# RasPiTimePowerSWv_1_6.net
KiCad netlist of a schematic drawn in EAGLE
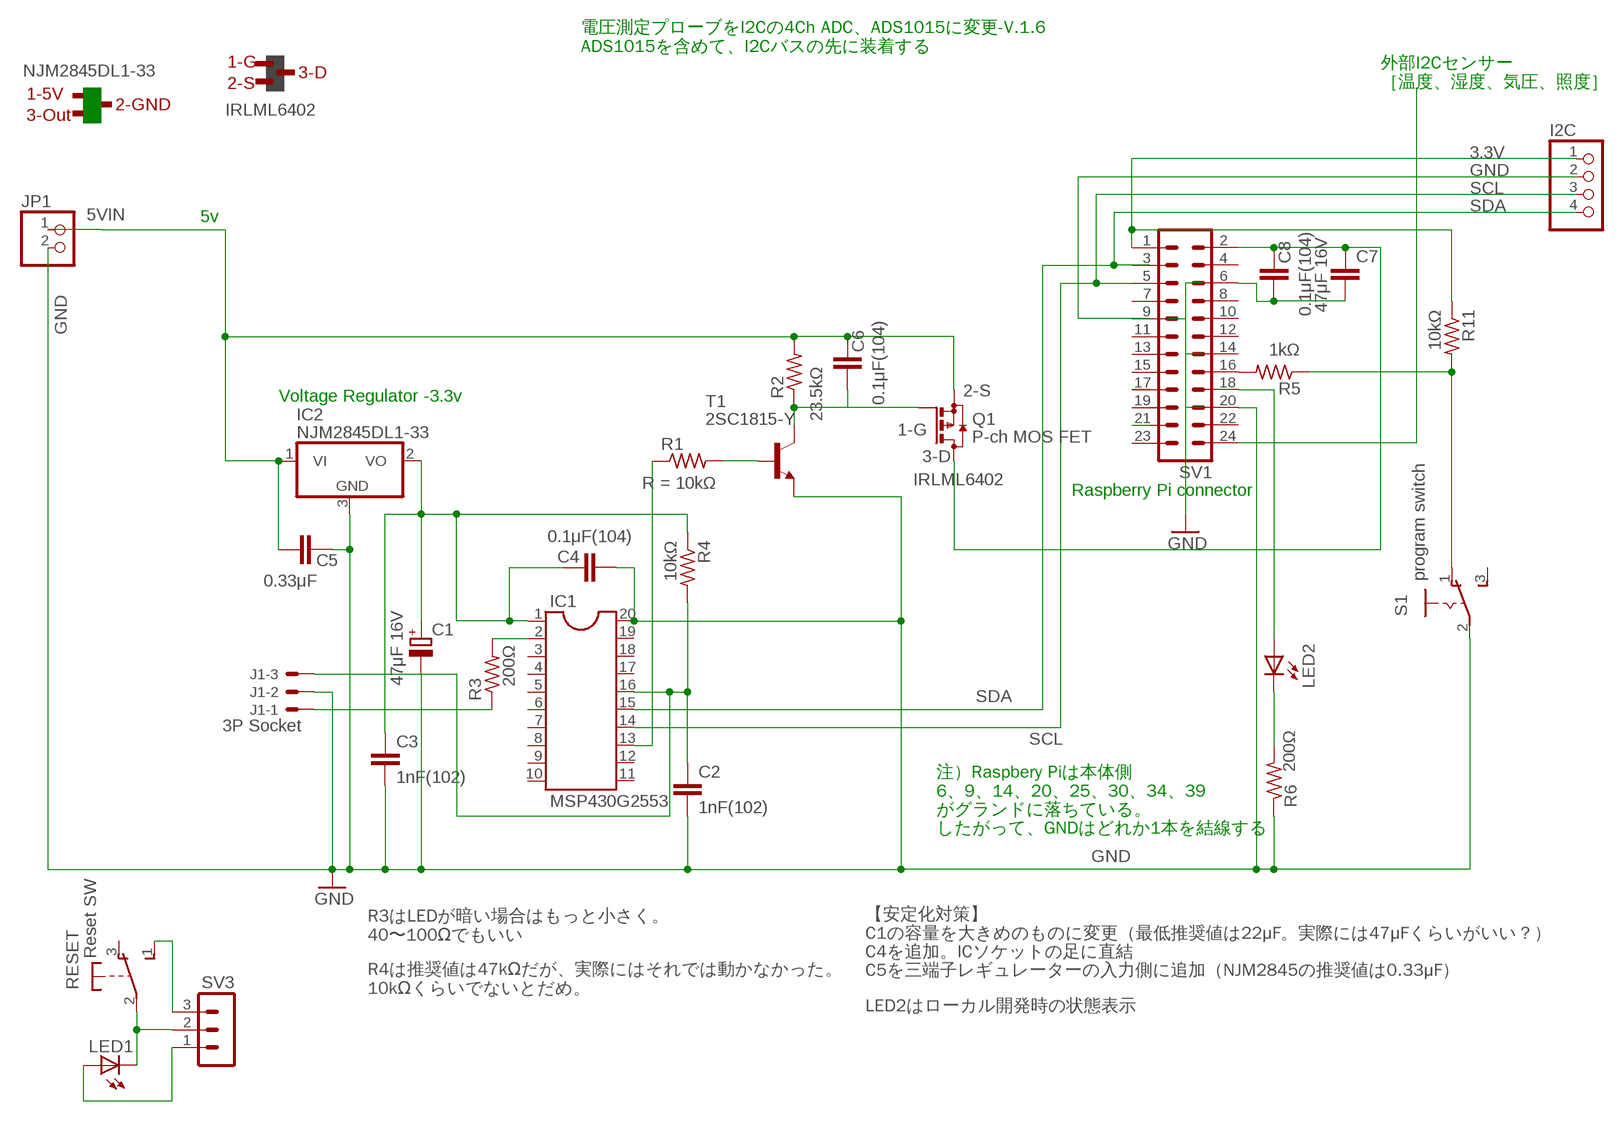
[diagram p0: schematic, sheet 1]

(export (version "E")
  (design (tool "Eeschema 10.0.6"))
  (components
    (comp (ref "C1")
      (value "47μF 16V")
      (footprint "eagle-import:153CLV-0605")
      (libsource (lib "eagle-import") (part "CPOL-EU153CLV-0605"))
    )
    (comp (ref "C2")
      (value "1nF(102)")
      (footprint "eagle-import:C025-024X044")
      (libsource (lib "eagle-import") (part "C-EU025-024X044"))
    )
    (comp (ref "C3")
      (value "1nF(102)")
      (footprint "eagle-import:C025-024X044")
      (libsource (lib "eagle-import") (part "C-EU025-024X044"))
    )
    (comp (ref "C4")
      (value "0.1μF(104)")
      (footprint "eagle-import:C025-024X044")
      (libsource (lib "eagle-import") (part "C-EU025-024X044"))
    )
    (comp (ref "C5")
      (value "0.33μF")
      (footprint "eagle-import:C025-024X044")
      (libsource (lib "eagle-import") (part "C-EU025-024X044"))
    )
    (comp (ref "C6")
      (value "0.1μF(104)")
      (footprint "eagle-import:C025-024X044")
      (libsource (lib "eagle-import") (part "C-EU025-024X044"))
    )
    (comp (ref "C7")
      (value "47μF 16V")
      (footprint "eagle-import:C075-042X103")
      (libsource (lib "eagle-import") (part "C-EU075-042X103"))
    )
    (comp (ref "C8")
      (value "0.1μF(104)")
      (footprint "eagle-import:C025-024X044")
      (libsource (lib "eagle-import") (part "C-EU025-024X044"))
    )
    (comp (ref "I2C")
      (value "PINHD-1X4")
      (footprint "eagle-import:1X04")
      (libsource (lib "eagle-import") (part "PINHD-1X4"))
    )
    (comp (ref "IC1")
      (value "MSP430G2553")
      (footprint "eagle-import:SOCKET-20")
      (libsource (lib "eagle-import") (part "DIL20S"))
    )
    (comp (ref "IC2")
      (value "NJM2845DL1-33")
      (footprint "eagle-import:TO252")
      (libsource (lib "eagle-import") (part "78DT05"))
    )
    (comp (ref "J1")
      (value "3P Socket")
      (footprint "eagle-import:6410-03")
      (libsource (lib "eagle-import") (part "22-?-0327-2031"))
    )
    (comp (ref "JP1")
      (value "PINHD-1X2")
      (footprint "eagle-import:1X02")
      (libsource (lib "eagle-import") (part "PINHD-1X2"))
    )
    (comp (ref "LED1")
      (value "TLLG4400")
      (footprint "eagle-import:LED3MM")
      (fields (field (name "MF") "VISHAY SEMICONDUCTOR"))
      (libsource (lib "eagle-import") (part "TLLG4400"))
    )
    (comp (ref "LED2")
      (value "TLLG4400")
      (footprint "eagle-import:LED3MM")
      (fields (field (name "MF") "VISHAY SEMICONDUCTOR"))
      (libsource (lib "eagle-import") (part "TLLG4400"))
    )
    (comp (ref "Q1")
      (value "P-ch MOS FET")
      (footprint "eagle-import:SOT23")
      (libsource (lib "eagle-import") (part "BSS84"))
    )
    (comp (ref "R1")
      (value "R-US_MELF0102W")
      (footprint "eagle-import:MINI_MELF-0102W")
      (fields (field (name "R") "10kΩ"))
      (libsource (lib "eagle-import") (part "R-US_MELF0102W"))
    )
    (comp (ref "R2")
      (value "R-US_MELF0102W")
      (footprint "eagle-import:MINI_MELF-0102W")
      (fields (field (name "1K") "23.5kΩ"))
      (libsource (lib "eagle-import") (part "R-US_MELF0102W"))
    )
    (comp (ref "R3")
      (value "R-US_MELF0102W")
      (footprint "eagle-import:MINI_MELF-0102W")
      (fields (field (name "R") "200Ω"))
      (libsource (lib "eagle-import") (part "R-US_MELF0102W"))
    )
    (comp (ref "R4")
      (value "10kΩ")
      (footprint "eagle-import:MINI_MELF-0102W")
      (libsource (lib "eagle-import") (part "R-US_MELF0102W"))
    )
    (comp (ref "R5")
      (value "R-US_MELF0102W")
      (footprint "eagle-import:MINI_MELF-0102W")
      (fields (field (name "1K") "1kΩ"))
      (libsource (lib "eagle-import") (part "R-US_MELF0102W"))
    )
    (comp (ref "R6")
      (value "R-US_MELF0102W")
      (footprint "eagle-import:MINI_MELF-0102W")
      (fields (field (name "R") "200Ω"))
      (libsource (lib "eagle-import") (part "R-US_MELF0102W"))
    )
    (comp (ref "R11")
      (value "10kΩ")
      (footprint "eagle-import:MINI_MELF-0102W")
      (libsource (lib "eagle-import") (part "R-US_MELF0102W"))
    )
    (comp (ref "RESET")
      (value "Reset SW")
      (footprint "eagle-import:9450-1")
      (libsource (lib "eagle-import") (part "9450-1"))
    )
    (comp (ref "S1")
      (value "program switch")
      (footprint "eagle-import:255SB")
      (libsource (lib "eagle-import") (part "255SB"))
    )
    (comp (ref "SV1")
      (value "MA12-2")
      (footprint "eagle-import:MA12-2")
      (libsource (lib "eagle-import") (part "MA12-2"))
    )
    (comp (ref "SV3")
      (value "MA03-1")
      (footprint "eagle-import:MA03-1")
      (libsource (lib "eagle-import") (part "MA03-1"))
    )
    (comp (ref "T1")
      (value "2SC1815-Y")
      (footprint "eagle-import:TO92-ECB")
      (libsource (lib "eagle-import") (part "2SC1815"))
    )
  )
  (nets
    (net (code "1") (name "/3.3V") (class "Default")
      (node (ref "C1") (pin "+") (pinfunction "+_+") (pintype "passive"))
      (node (ref "C3") (pin "1") (pinfunction "1_1") (pintype "passive"))
      (node (ref "C4") (pin "1") (pinfunction "1_1") (pintype "passive"))
      (node (ref "I2C") (pin "1") (pinfunction "1_1") (pintype "passive"))
      (node (ref "IC1") (pin "1") (pinfunction "1_1") (pintype "passive"))
      (node (ref "IC2") (pin "2") (pinfunction "VO_2") (pintype "passive"))
      (node (ref "R11") (pin "1") (pinfunction "1_1") (pintype "passive"))
      (node (ref "R4") (pin "1") (pinfunction "1_1") (pintype "passive"))
      (node (ref "SV1") (pin "1") (pinfunction "1_1") (pintype "passive"))
    )
    (net (code "2") (name "/5VIN") (class "Default")
      (node (ref "C5") (pin "2") (pinfunction "2_2") (pintype "passive"))
      (node (ref "C6") (pin "1") (pinfunction "1_1") (pintype "passive"))
      (node (ref "IC2") (pin "1") (pinfunction "VI_1") (pintype "input"))
      (node (ref "JP1") (pin "1") (pinfunction "1_1") (pintype "passive"))
      (node (ref "Q1") (pin "2") (pinfunction "S_2") (pintype "passive"))
      (node (ref "R2") (pin "2") (pinfunction "2_2") (pintype "passive"))
    )
    (net (code "3") (name "/SCL") (class "Default")
      (node (ref "I2C") (pin "3") (pinfunction "3_3") (pintype "passive"))
      (node (ref "IC1") (pin "14") (pinfunction "14_14") (pintype "passive"))
      (node (ref "SV1") (pin "5") (pinfunction "5_5") (pintype "passive"))
    )
    (net (code "4") (name "/SDA") (class "Default")
      (node (ref "I2C") (pin "4") (pinfunction "4_4") (pintype "passive"))
      (node (ref "IC1") (pin "15") (pinfunction "15_15") (pintype "passive"))
      (node (ref "SV1") (pin "3") (pinfunction "3_3") (pintype "passive"))
    )
    (net (code "5") (name "GND") (class "Default")
      (node (ref "C1") (pin "-") (pinfunction "-_-") (pintype "passive"))
      (node (ref "C2") (pin "2") (pinfunction "2_2") (pintype "passive"))
      (node (ref "C3") (pin "2") (pinfunction "2_2") (pintype "passive"))
      (node (ref "C4") (pin "2") (pinfunction "2_2") (pintype "passive"))
      (node (ref "C5") (pin "1") (pinfunction "1_1") (pintype "passive"))
      (node (ref "I2C") (pin "2") (pinfunction "2_2") (pintype "passive"))
      (node (ref "IC1") (pin "20") (pinfunction "20_20") (pintype "passive"))
      (node (ref "IC2") (pin "3") (pinfunction "GND_3") (pintype "passive"))
      (node (ref "J1") (pin "2") (pinfunction "S_2") (pintype "passive"))
      (node (ref "JP1") (pin "2") (pinfunction "2_2") (pintype "passive"))
      (node (ref "R6") (pin "1") (pinfunction "1_1") (pintype "passive"))
      (node (ref "S1") (pin "2") (pinfunction "P_2") (pintype "passive"))
      (node (ref "SV1") (pin "20") (pinfunction "20_20") (pintype "passive"))
      (node (ref "SV1") (pin "9") (pinfunction "9_9") (pintype "passive"))
      (node (ref "T1") (pin "E") (pinfunction "E_E") (pintype "passive"))
    )
    (net (code "6") (name "Net-(C7-Pad2)") (class "Default")
      (node (ref "C7") (pin "2") (pinfunction "2_2") (pintype "passive"))
      (node (ref "C8") (pin "2") (pinfunction "2_2") (pintype "passive"))
      (node (ref "SV1") (pin "6") (pinfunction "6_6") (pintype "passive"))
    )
    (net (code "7") (name "Net-(IC1-Pad2)") (class "Default")
      (node (ref "IC1") (pin "2") (pinfunction "2_2") (pintype "passive"))
      (node (ref "R3") (pin "2") (pinfunction "2_2") (pintype "passive"))
    )
    (net (code "8") (name "Net-(IC1-Pad13)") (class "Default")
      (node (ref "IC1") (pin "13") (pinfunction "13_13") (pintype "passive"))
      (node (ref "R1") (pin "1") (pinfunction "1_1") (pintype "passive"))
    )
    (net (code "9") (name "Net-(J1A-S)") (class "Default")
      (node (ref "J1") (pin "1") (pinfunction "S_1") (pintype "passive"))
      (node (ref "R3") (pin "1") (pinfunction "1_1") (pintype "passive"))
    )
    (net (code "10") (name "Net-(J1C-S)") (class "Default")
      (node (ref "C2") (pin "1") (pinfunction "1_1") (pintype "passive"))
      (node (ref "IC1") (pin "16") (pinfunction "16_16") (pintype "passive"))
      (node (ref "J1") (pin "3") (pinfunction "S_3") (pintype "passive"))
      (node (ref "R4") (pin "2") (pinfunction "2_2") (pintype "passive"))
    )
    (net (code "11") (name "Net-(LED1-C)") (class "Default")
      (node (ref "LED1") (pin "K") (pinfunction "C_K") (pintype "passive"))
      (node (ref "RESET") (pin "2") (pinfunction "P_2") (pintype "passive"))
      (node (ref "SV3") (pin "2") (pinfunction "2_2") (pintype "passive"))
    )
    (net (code "12") (name "Net-(LED1-PadA)") (class "Default")
      (node (ref "LED1") (pin "A") (pinfunction "A_A") (pintype "passive"))
      (node (ref "SV3") (pin "1") (pinfunction "1_1") (pintype "passive"))
    )
    (net (code "13") (name "Net-(LED2-C)") (class "Default")
      (node (ref "LED2") (pin "K") (pinfunction "C_K") (pintype "passive"))
      (node (ref "R6") (pin "2") (pinfunction "2_2") (pintype "passive"))
    )
    (net (code "14") (name "Net-(LED2-PadA)") (class "Default")
      (node (ref "LED2") (pin "A") (pinfunction "A_A") (pintype "passive"))
      (node (ref "SV1") (pin "18") (pinfunction "18_18") (pintype "passive"))
    )
    (net (code "15") (name "Net-(Q1-D)") (class "Default")
      (node (ref "C7") (pin "1") (pinfunction "1_1") (pintype "passive"))
      (node (ref "C8") (pin "1") (pinfunction "1_1") (pintype "passive"))
      (node (ref "Q1") (pin "3") (pinfunction "D_3") (pintype "passive"))
      (node (ref "SV1") (pin "2") (pinfunction "2_2") (pintype "passive"))
    )
    (net (code "16") (name "Net-(Q1-G)") (class "Default")
      (node (ref "C6") (pin "2") (pinfunction "2_2") (pintype "passive"))
      (node (ref "Q1") (pin "1") (pinfunction "G_1") (pintype "passive"))
      (node (ref "R2") (pin "1") (pinfunction "1_1") (pintype "passive"))
      (node (ref "T1") (pin "C") (pinfunction "C_C") (pintype "passive"))
    )
    (net (code "17") (name "Net-(R1-Pad2)") (class "Default")
      (node (ref "R1") (pin "2") (pinfunction "2_2") (pintype "passive"))
      (node (ref "T1") (pin "B") (pinfunction "B_B") (pintype "passive"))
    )
    (net (code "18") (name "Net-(R5-Pad2)") (class "Default")
      (node (ref "R5") (pin "2") (pinfunction "2_2") (pintype "passive"))
      (node (ref "SV1") (pin "16") (pinfunction "16_16") (pintype "passive"))
    )
    (net (code "19") (name "Net-(RESET-S)") (class "Default")
      (node (ref "RESET") (pin "1") (pinfunction "S_1") (pintype "passive"))
      (node (ref "SV3") (pin "3") (pinfunction "3_3") (pintype "passive"))
    )
    (net (code "20") (name "Net-(S1-O)") (class "Default")
      (node (ref "R11") (pin "2") (pinfunction "2_2") (pintype "passive"))
      (node (ref "R5") (pin "1") (pinfunction "1_1") (pintype "passive"))
      (node (ref "S1") (pin "1") (pinfunction "O_1") (pintype "passive"))
    )
    (net (code "21") (name "unconnected-(IC1-Pad3)") (class "Default")
      (node (ref "IC1") (pin "3") (pinfunction "3_3") (pintype "passive"))
    )
    (net (code "22") (name "unconnected-(IC1-Pad4)") (class "Default")
      (node (ref "IC1") (pin "4") (pinfunction "4_4") (pintype "passive"))
    )
    (net (code "23") (name "unconnected-(IC1-Pad5)") (class "Default")
      (node (ref "IC1") (pin "5") (pinfunction "5_5") (pintype "passive"))
    )
    (net (code "24") (name "unconnected-(IC1-Pad6)") (class "Default")
      (node (ref "IC1") (pin "6") (pinfunction "6_6") (pintype "passive"))
    )
    (net (code "25") (name "unconnected-(IC1-Pad7)") (class "Default")
      (node (ref "IC1") (pin "7") (pinfunction "7_7") (pintype "passive"))
    )
    (net (code "26") (name "unconnected-(IC1-Pad8)") (class "Default")
      (node (ref "IC1") (pin "8") (pinfunction "8_8") (pintype "passive"))
    )
    (net (code "27") (name "unconnected-(IC1-Pad9)") (class "Default")
      (node (ref "IC1") (pin "9") (pinfunction "9_9") (pintype "passive"))
    )
    (net (code "28") (name "unconnected-(IC1-Pad10)") (class "Default")
      (node (ref "IC1") (pin "10") (pinfunction "10_10") (pintype "passive"))
    )
    (net (code "29") (name "unconnected-(IC1-Pad11)") (class "Default")
      (node (ref "IC1") (pin "11") (pinfunction "11_11") (pintype "passive"))
    )
    (net (code "30") (name "unconnected-(IC1-Pad12)") (class "Default")
      (node (ref "IC1") (pin "12") (pinfunction "12_12") (pintype "passive"))
    )
    (net (code "31") (name "unconnected-(IC1-Pad17)") (class "Default")
      (node (ref "IC1") (pin "17") (pinfunction "17_17") (pintype "passive"))
    )
    (net (code "32") (name "unconnected-(IC1-Pad18)") (class "Default")
      (node (ref "IC1") (pin "18") (pinfunction "18_18") (pintype "passive"))
    )
    (net (code "33") (name "unconnected-(IC1-Pad19)") (class "Default")
      (node (ref "IC1") (pin "19") (pinfunction "19_19") (pintype "passive"))
    )
    (net (code "34") (name "unconnected-(RESET-O-Pad3)") (class "Default")
      (node (ref "RESET") (pin "3") (pinfunction "O_3") (pintype "passive"))
    )
    (net (code "35") (name "unconnected-(S1-S-Pad3)") (class "Default")
      (node (ref "S1") (pin "3") (pinfunction "S_3") (pintype "passive"))
    )
    (net (code "36") (name "unconnected-(SV1-Pad4)") (class "Default")
      (node (ref "SV1") (pin "4") (pinfunction "4_4") (pintype "passive"))
    )
    (net (code "37") (name "unconnected-(SV1-Pad7)") (class "Default")
      (node (ref "SV1") (pin "7") (pinfunction "7_7") (pintype "passive"))
    )
    (net (code "38") (name "unconnected-(SV1-Pad8)") (class "Default")
      (node (ref "SV1") (pin "8") (pinfunction "8_8") (pintype "passive"))
    )
    (net (code "39") (name "unconnected-(SV1-Pad10)") (class "Default")
      (node (ref "SV1") (pin "10") (pinfunction "10_10") (pintype "passive"))
    )
    (net (code "40") (name "unconnected-(SV1-Pad11)") (class "Default")
      (node (ref "SV1") (pin "11") (pinfunction "11_11") (pintype "passive"))
    )
    (net (code "41") (name "unconnected-(SV1-Pad12)") (class "Default")
      (node (ref "SV1") (pin "12") (pinfunction "12_12") (pintype "passive"))
    )
    (net (code "42") (name "unconnected-(SV1-Pad13)") (class "Default")
      (node (ref "SV1") (pin "13") (pinfunction "13_13") (pintype "passive"))
    )
    (net (code "43") (name "unconnected-(SV1-Pad14)") (class "Default")
      (node (ref "SV1") (pin "14") (pinfunction "14_14") (pintype "passive"))
    )
    (net (code "44") (name "unconnected-(SV1-Pad15)") (class "Default")
      (node (ref "SV1") (pin "15") (pinfunction "15_15") (pintype "passive"))
    )
    (net (code "45") (name "unconnected-(SV1-Pad17)") (class "Default")
      (node (ref "SV1") (pin "17") (pinfunction "17_17") (pintype "passive"))
    )
    (net (code "46") (name "unconnected-(SV1-Pad19)") (class "Default")
      (node (ref "SV1") (pin "19") (pinfunction "19_19") (pintype "passive"))
    )
    (net (code "47") (name "unconnected-(SV1-Pad21)") (class "Default")
      (node (ref "SV1") (pin "21") (pinfunction "21_21") (pintype "passive"))
    )
    (net (code "48") (name "unconnected-(SV1-Pad22)") (class "Default")
      (node (ref "SV1") (pin "22") (pinfunction "22_22") (pintype "passive"))
    )
    (net (code "49") (name "unconnected-(SV1-Pad23)") (class "Default")
      (node (ref "SV1") (pin "23") (pinfunction "23_23") (pintype "passive"))
    )
    (net (code "50") (name "unconnected-(SV1-Pad24)") (class "Default")
      (node (ref "SV1") (pin "24") (pinfunction "24_24") (pintype "passive"))
    )
  )
)
